# SMSL0208.net
KiCad netlist of a schematic drawn in EAGLE
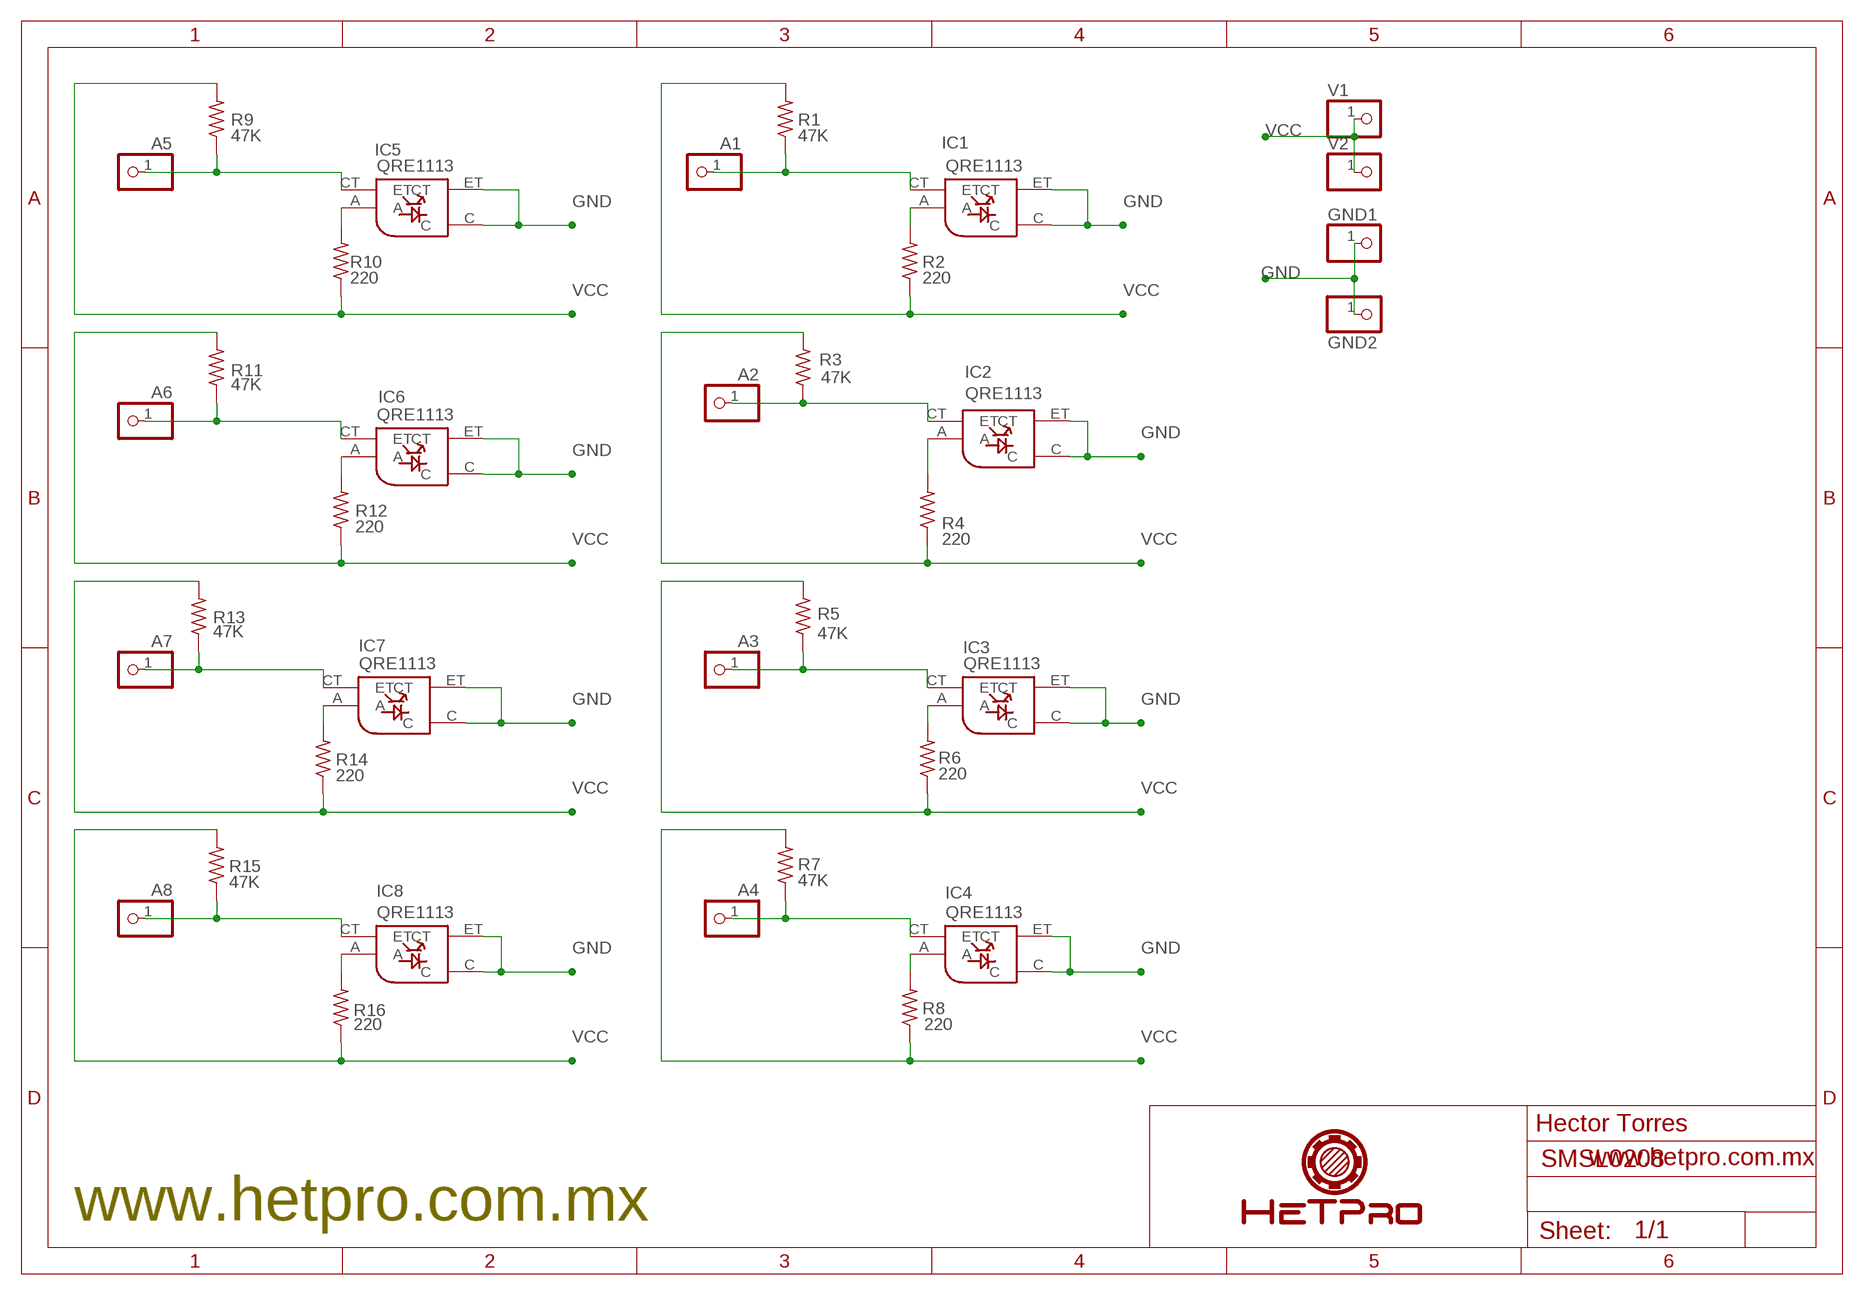
[diagram p0: schematic, sheet 1]

(export (version "E")
  (design (tool "Eeschema 10.0.6"))
  (components
    (comp (ref "A1")
      (value "PINHD-1X1")
      (footprint "eagle-import:1X01")
      (libsource (lib "eagle-import") (part "PINHD-1X1"))
    )
    (comp (ref "A2")
      (value "PINHD-1X1")
      (footprint "eagle-import:1X01")
      (libsource (lib "eagle-import") (part "PINHD-1X1"))
    )
    (comp (ref "A3")
      (value "PINHD-1X1")
      (footprint "eagle-import:1X01")
      (libsource (lib "eagle-import") (part "PINHD-1X1"))
    )
    (comp (ref "A4")
      (value "PINHD-1X1")
      (footprint "eagle-import:1X01")
      (libsource (lib "eagle-import") (part "PINHD-1X1"))
    )
    (comp (ref "A5")
      (value "PINHD-1X1")
      (footprint "eagle-import:1X01")
      (libsource (lib "eagle-import") (part "PINHD-1X1"))
    )
    (comp (ref "A6")
      (value "PINHD-1X1")
      (footprint "eagle-import:1X01")
      (libsource (lib "eagle-import") (part "PINHD-1X1"))
    )
    (comp (ref "A7")
      (value "PINHD-1X1")
      (footprint "eagle-import:1X01")
      (libsource (lib "eagle-import") (part "PINHD-1X1"))
    )
    (comp (ref "A8")
      (value "PINHD-1X1")
      (footprint "eagle-import:1X01")
      (libsource (lib "eagle-import") (part "PINHD-1X1"))
    )
    (comp (ref "GND1")
      (value "PINHD-1X1")
      (footprint "eagle-import:1X01")
      (libsource (lib "eagle-import") (part "PINHD-1X1"))
    )
    (comp (ref "GND2")
      (value "PINHD-1X1")
      (footprint "eagle-import:1X01")
      (libsource (lib "eagle-import") (part "PINHD-1X1"))
    )
    (comp (ref "IC1")
      (value "QRE1113")
      (footprint "eagle-import:QRE1113")
      (libsource (lib "eagle-import") (part "QRE1113"))
    )
    (comp (ref "IC2")
      (value "QRE1113")
      (footprint "eagle-import:QRE1113")
      (libsource (lib "eagle-import") (part "QRE1113"))
    )
    (comp (ref "IC3")
      (value "QRE1113")
      (footprint "eagle-import:QRE1113")
      (libsource (lib "eagle-import") (part "QRE1113"))
    )
    (comp (ref "IC4")
      (value "QRE1113")
      (footprint "eagle-import:QRE1113")
      (libsource (lib "eagle-import") (part "QRE1113"))
    )
    (comp (ref "IC5")
      (value "QRE1113")
      (footprint "eagle-import:QRE1113")
      (libsource (lib "eagle-import") (part "QRE1113"))
    )
    (comp (ref "IC6")
      (value "QRE1113")
      (footprint "eagle-import:QRE1113")
      (libsource (lib "eagle-import") (part "QRE1113"))
    )
    (comp (ref "IC7")
      (value "QRE1113")
      (footprint "eagle-import:QRE1113")
      (libsource (lib "eagle-import") (part "QRE1113"))
    )
    (comp (ref "IC8")
      (value "QRE1113")
      (footprint "eagle-import:QRE1113")
      (libsource (lib "eagle-import") (part "QRE1113"))
    )
    (comp (ref "R1")
      (value "47K")
      (footprint "eagle-import:R0603")
      (libsource (lib "eagle-import") (part "R-US_R0603"))
    )
    (comp (ref "R2")
      (value "220")
      (footprint "eagle-import:R0603")
      (libsource (lib "eagle-import") (part "R-US_R0603"))
    )
    (comp (ref "R3")
      (value "47K")
      (footprint "eagle-import:R0603")
      (libsource (lib "eagle-import") (part "R-US_R0603"))
    )
    (comp (ref "R4")
      (value "220")
      (footprint "eagle-import:R0603")
      (libsource (lib "eagle-import") (part "R-US_R0603"))
    )
    (comp (ref "R5")
      (value "47K")
      (footprint "eagle-import:R0603")
      (libsource (lib "eagle-import") (part "R-US_R0603"))
    )
    (comp (ref "R6")
      (value "220")
      (footprint "eagle-import:R0603")
      (libsource (lib "eagle-import") (part "R-US_R0603"))
    )
    (comp (ref "R7")
      (value "47K")
      (footprint "eagle-import:R0603")
      (libsource (lib "eagle-import") (part "R-US_R0603"))
    )
    (comp (ref "R8")
      (value "220")
      (footprint "eagle-import:R0603")
      (libsource (lib "eagle-import") (part "R-US_R0603"))
    )
    (comp (ref "R9")
      (value "47K")
      (footprint "eagle-import:R0603")
      (libsource (lib "eagle-import") (part "R-US_R0603"))
    )
    (comp (ref "R10")
      (value "220")
      (footprint "eagle-import:R0603")
      (libsource (lib "eagle-import") (part "R-US_R0603"))
    )
    (comp (ref "R11")
      (value "47K")
      (footprint "eagle-import:R0603")
      (libsource (lib "eagle-import") (part "R-US_R0603"))
    )
    (comp (ref "R12")
      (value "220")
      (footprint "eagle-import:R0603")
      (libsource (lib "eagle-import") (part "R-US_R0603"))
    )
    (comp (ref "R13")
      (value "47K")
      (footprint "eagle-import:R0603")
      (libsource (lib "eagle-import") (part "R-US_R0603"))
    )
    (comp (ref "R14")
      (value "220")
      (footprint "eagle-import:R0603")
      (libsource (lib "eagle-import") (part "R-US_R0603"))
    )
    (comp (ref "R15")
      (value "47K")
      (footprint "eagle-import:R0603")
      (libsource (lib "eagle-import") (part "R-US_R0603"))
    )
    (comp (ref "R16")
      (value "220")
      (footprint "eagle-import:R0603")
      (libsource (lib "eagle-import") (part "R-US_R0603"))
    )
    (comp (ref "V1")
      (value "PINHD-1X1")
      (footprint "eagle-import:1X01")
      (libsource (lib "eagle-import") (part "PINHD-1X1"))
    )
    (comp (ref "V2")
      (value "PINHD-1X1")
      (footprint "eagle-import:1X01")
      (libsource (lib "eagle-import") (part "PINHD-1X1"))
    )
  )
  (nets
    (net (code "1") (name "/GND") (class "Default")
      (node (ref "GND1") (pin "1") (pinfunction "1_1") (pintype "passive"))
      (node (ref "GND2") (pin "1") (pinfunction "1_1") (pintype "passive"))
      (node (ref "IC1") (pin "C") (pinfunction "C_C") (pintype "bidirectional"))
      (node (ref "IC1") (pin "ET") (pinfunction "CT_ET") (pintype "bidirectional"))
      (node (ref "IC2") (pin "C") (pinfunction "C_C") (pintype "bidirectional"))
      (node (ref "IC2") (pin "ET") (pinfunction "CT_ET") (pintype "bidirectional"))
      (node (ref "IC3") (pin "C") (pinfunction "C_C") (pintype "bidirectional"))
      (node (ref "IC3") (pin "ET") (pinfunction "CT_ET") (pintype "bidirectional"))
      (node (ref "IC4") (pin "C") (pinfunction "C_C") (pintype "bidirectional"))
      (node (ref "IC4") (pin "ET") (pinfunction "CT_ET") (pintype "bidirectional"))
      (node (ref "IC5") (pin "C") (pinfunction "C_C") (pintype "bidirectional"))
      (node (ref "IC5") (pin "ET") (pinfunction "CT_ET") (pintype "bidirectional"))
      (node (ref "IC6") (pin "C") (pinfunction "C_C") (pintype "bidirectional"))
      (node (ref "IC6") (pin "ET") (pinfunction "CT_ET") (pintype "bidirectional"))
      (node (ref "IC7") (pin "C") (pinfunction "C_C") (pintype "bidirectional"))
      (node (ref "IC7") (pin "ET") (pinfunction "CT_ET") (pintype "bidirectional"))
      (node (ref "IC8") (pin "C") (pinfunction "C_C") (pintype "bidirectional"))
      (node (ref "IC8") (pin "ET") (pinfunction "CT_ET") (pintype "bidirectional"))
    )
    (net (code "2") (name "/VCC") (class "Default")
      (node (ref "R1") (pin "2") (pinfunction "2_2") (pintype "passive"))
      (node (ref "R10") (pin "1") (pinfunction "1_1") (pintype "passive"))
      (node (ref "R11") (pin "2") (pinfunction "2_2") (pintype "passive"))
      (node (ref "R12") (pin "1") (pinfunction "1_1") (pintype "passive"))
      (node (ref "R13") (pin "2") (pinfunction "2_2") (pintype "passive"))
      (node (ref "R14") (pin "1") (pinfunction "1_1") (pintype "passive"))
      (node (ref "R15") (pin "2") (pinfunction "2_2") (pintype "passive"))
      (node (ref "R16") (pin "1") (pinfunction "1_1") (pintype "passive"))
      (node (ref "R2") (pin "1") (pinfunction "1_1") (pintype "passive"))
      (node (ref "R3") (pin "2") (pinfunction "2_2") (pintype "passive"))
      (node (ref "R4") (pin "1") (pinfunction "1_1") (pintype "passive"))
      (node (ref "R5") (pin "2") (pinfunction "2_2") (pintype "passive"))
      (node (ref "R6") (pin "1") (pinfunction "1_1") (pintype "passive"))
      (node (ref "R7") (pin "2") (pinfunction "2_2") (pintype "passive"))
      (node (ref "R8") (pin "1") (pinfunction "1_1") (pintype "passive"))
      (node (ref "R9") (pin "2") (pinfunction "2_2") (pintype "passive"))
      (node (ref "V1") (pin "1") (pinfunction "1_1") (pintype "passive"))
      (node (ref "V2") (pin "1") (pinfunction "1_1") (pintype "passive"))
    )
    (net (code "3") (name "Net-(IC1-ET)") (class "Default")
      (node (ref "A1") (pin "1") (pinfunction "1_1") (pintype "passive"))
      (node (ref "IC1") (pin "CT") (pinfunction "ET_CT") (pintype "bidirectional"))
      (node (ref "R1") (pin "1") (pinfunction "1_1") (pintype "passive"))
    )
    (net (code "4") (name "Net-(IC1-PadA)") (class "Default")
      (node (ref "IC1") (pin "A") (pinfunction "A_A") (pintype "bidirectional"))
      (node (ref "R2") (pin "2") (pinfunction "2_2") (pintype "passive"))
    )
    (net (code "5") (name "Net-(IC2-ET)") (class "Default")
      (node (ref "A2") (pin "1") (pinfunction "1_1") (pintype "passive"))
      (node (ref "IC2") (pin "CT") (pinfunction "ET_CT") (pintype "bidirectional"))
      (node (ref "R3") (pin "1") (pinfunction "1_1") (pintype "passive"))
    )
    (net (code "6") (name "Net-(IC2-PadA)") (class "Default")
      (node (ref "IC2") (pin "A") (pinfunction "A_A") (pintype "bidirectional"))
      (node (ref "R4") (pin "2") (pinfunction "2_2") (pintype "passive"))
    )
    (net (code "7") (name "Net-(IC3-ET)") (class "Default")
      (node (ref "A3") (pin "1") (pinfunction "1_1") (pintype "passive"))
      (node (ref "IC3") (pin "CT") (pinfunction "ET_CT") (pintype "bidirectional"))
      (node (ref "R5") (pin "1") (pinfunction "1_1") (pintype "passive"))
    )
    (net (code "8") (name "Net-(IC3-PadA)") (class "Default")
      (node (ref "IC3") (pin "A") (pinfunction "A_A") (pintype "bidirectional"))
      (node (ref "R6") (pin "2") (pinfunction "2_2") (pintype "passive"))
    )
    (net (code "9") (name "Net-(IC4-ET)") (class "Default")
      (node (ref "A4") (pin "1") (pinfunction "1_1") (pintype "passive"))
      (node (ref "IC4") (pin "CT") (pinfunction "ET_CT") (pintype "bidirectional"))
      (node (ref "R7") (pin "1") (pinfunction "1_1") (pintype "passive"))
    )
    (net (code "10") (name "Net-(IC4-PadA)") (class "Default")
      (node (ref "IC4") (pin "A") (pinfunction "A_A") (pintype "bidirectional"))
      (node (ref "R8") (pin "2") (pinfunction "2_2") (pintype "passive"))
    )
    (net (code "11") (name "Net-(IC5-ET)") (class "Default")
      (node (ref "A5") (pin "1") (pinfunction "1_1") (pintype "passive"))
      (node (ref "IC5") (pin "CT") (pinfunction "ET_CT") (pintype "bidirectional"))
      (node (ref "R9") (pin "1") (pinfunction "1_1") (pintype "passive"))
    )
    (net (code "12") (name "Net-(IC5-PadA)") (class "Default")
      (node (ref "IC5") (pin "A") (pinfunction "A_A") (pintype "bidirectional"))
      (node (ref "R10") (pin "2") (pinfunction "2_2") (pintype "passive"))
    )
    (net (code "13") (name "Net-(IC6-ET)") (class "Default")
      (node (ref "A6") (pin "1") (pinfunction "1_1") (pintype "passive"))
      (node (ref "IC6") (pin "CT") (pinfunction "ET_CT") (pintype "bidirectional"))
      (node (ref "R11") (pin "1") (pinfunction "1_1") (pintype "passive"))
    )
    (net (code "14") (name "Net-(IC6-PadA)") (class "Default")
      (node (ref "IC6") (pin "A") (pinfunction "A_A") (pintype "bidirectional"))
      (node (ref "R12") (pin "2") (pinfunction "2_2") (pintype "passive"))
    )
    (net (code "15") (name "Net-(IC7-ET)") (class "Default")
      (node (ref "A7") (pin "1") (pinfunction "1_1") (pintype "passive"))
      (node (ref "IC7") (pin "CT") (pinfunction "ET_CT") (pintype "bidirectional"))
      (node (ref "R13") (pin "1") (pinfunction "1_1") (pintype "passive"))
    )
    (net (code "16") (name "Net-(IC7-PadA)") (class "Default")
      (node (ref "IC7") (pin "A") (pinfunction "A_A") (pintype "bidirectional"))
      (node (ref "R14") (pin "2") (pinfunction "2_2") (pintype "passive"))
    )
    (net (code "17") (name "Net-(IC8-ET)") (class "Default")
      (node (ref "A8") (pin "1") (pinfunction "1_1") (pintype "passive"))
      (node (ref "IC8") (pin "CT") (pinfunction "ET_CT") (pintype "bidirectional"))
      (node (ref "R15") (pin "1") (pinfunction "1_1") (pintype "passive"))
    )
    (net (code "18") (name "Net-(IC8-PadA)") (class "Default")
      (node (ref "IC8") (pin "A") (pinfunction "A_A") (pintype "bidirectional"))
      (node (ref "R16") (pin "2") (pinfunction "2_2") (pintype "passive"))
    )
  )
)
